# Lesson1_2.net
KiCad netlist of a schematic drawn in EasyEDA
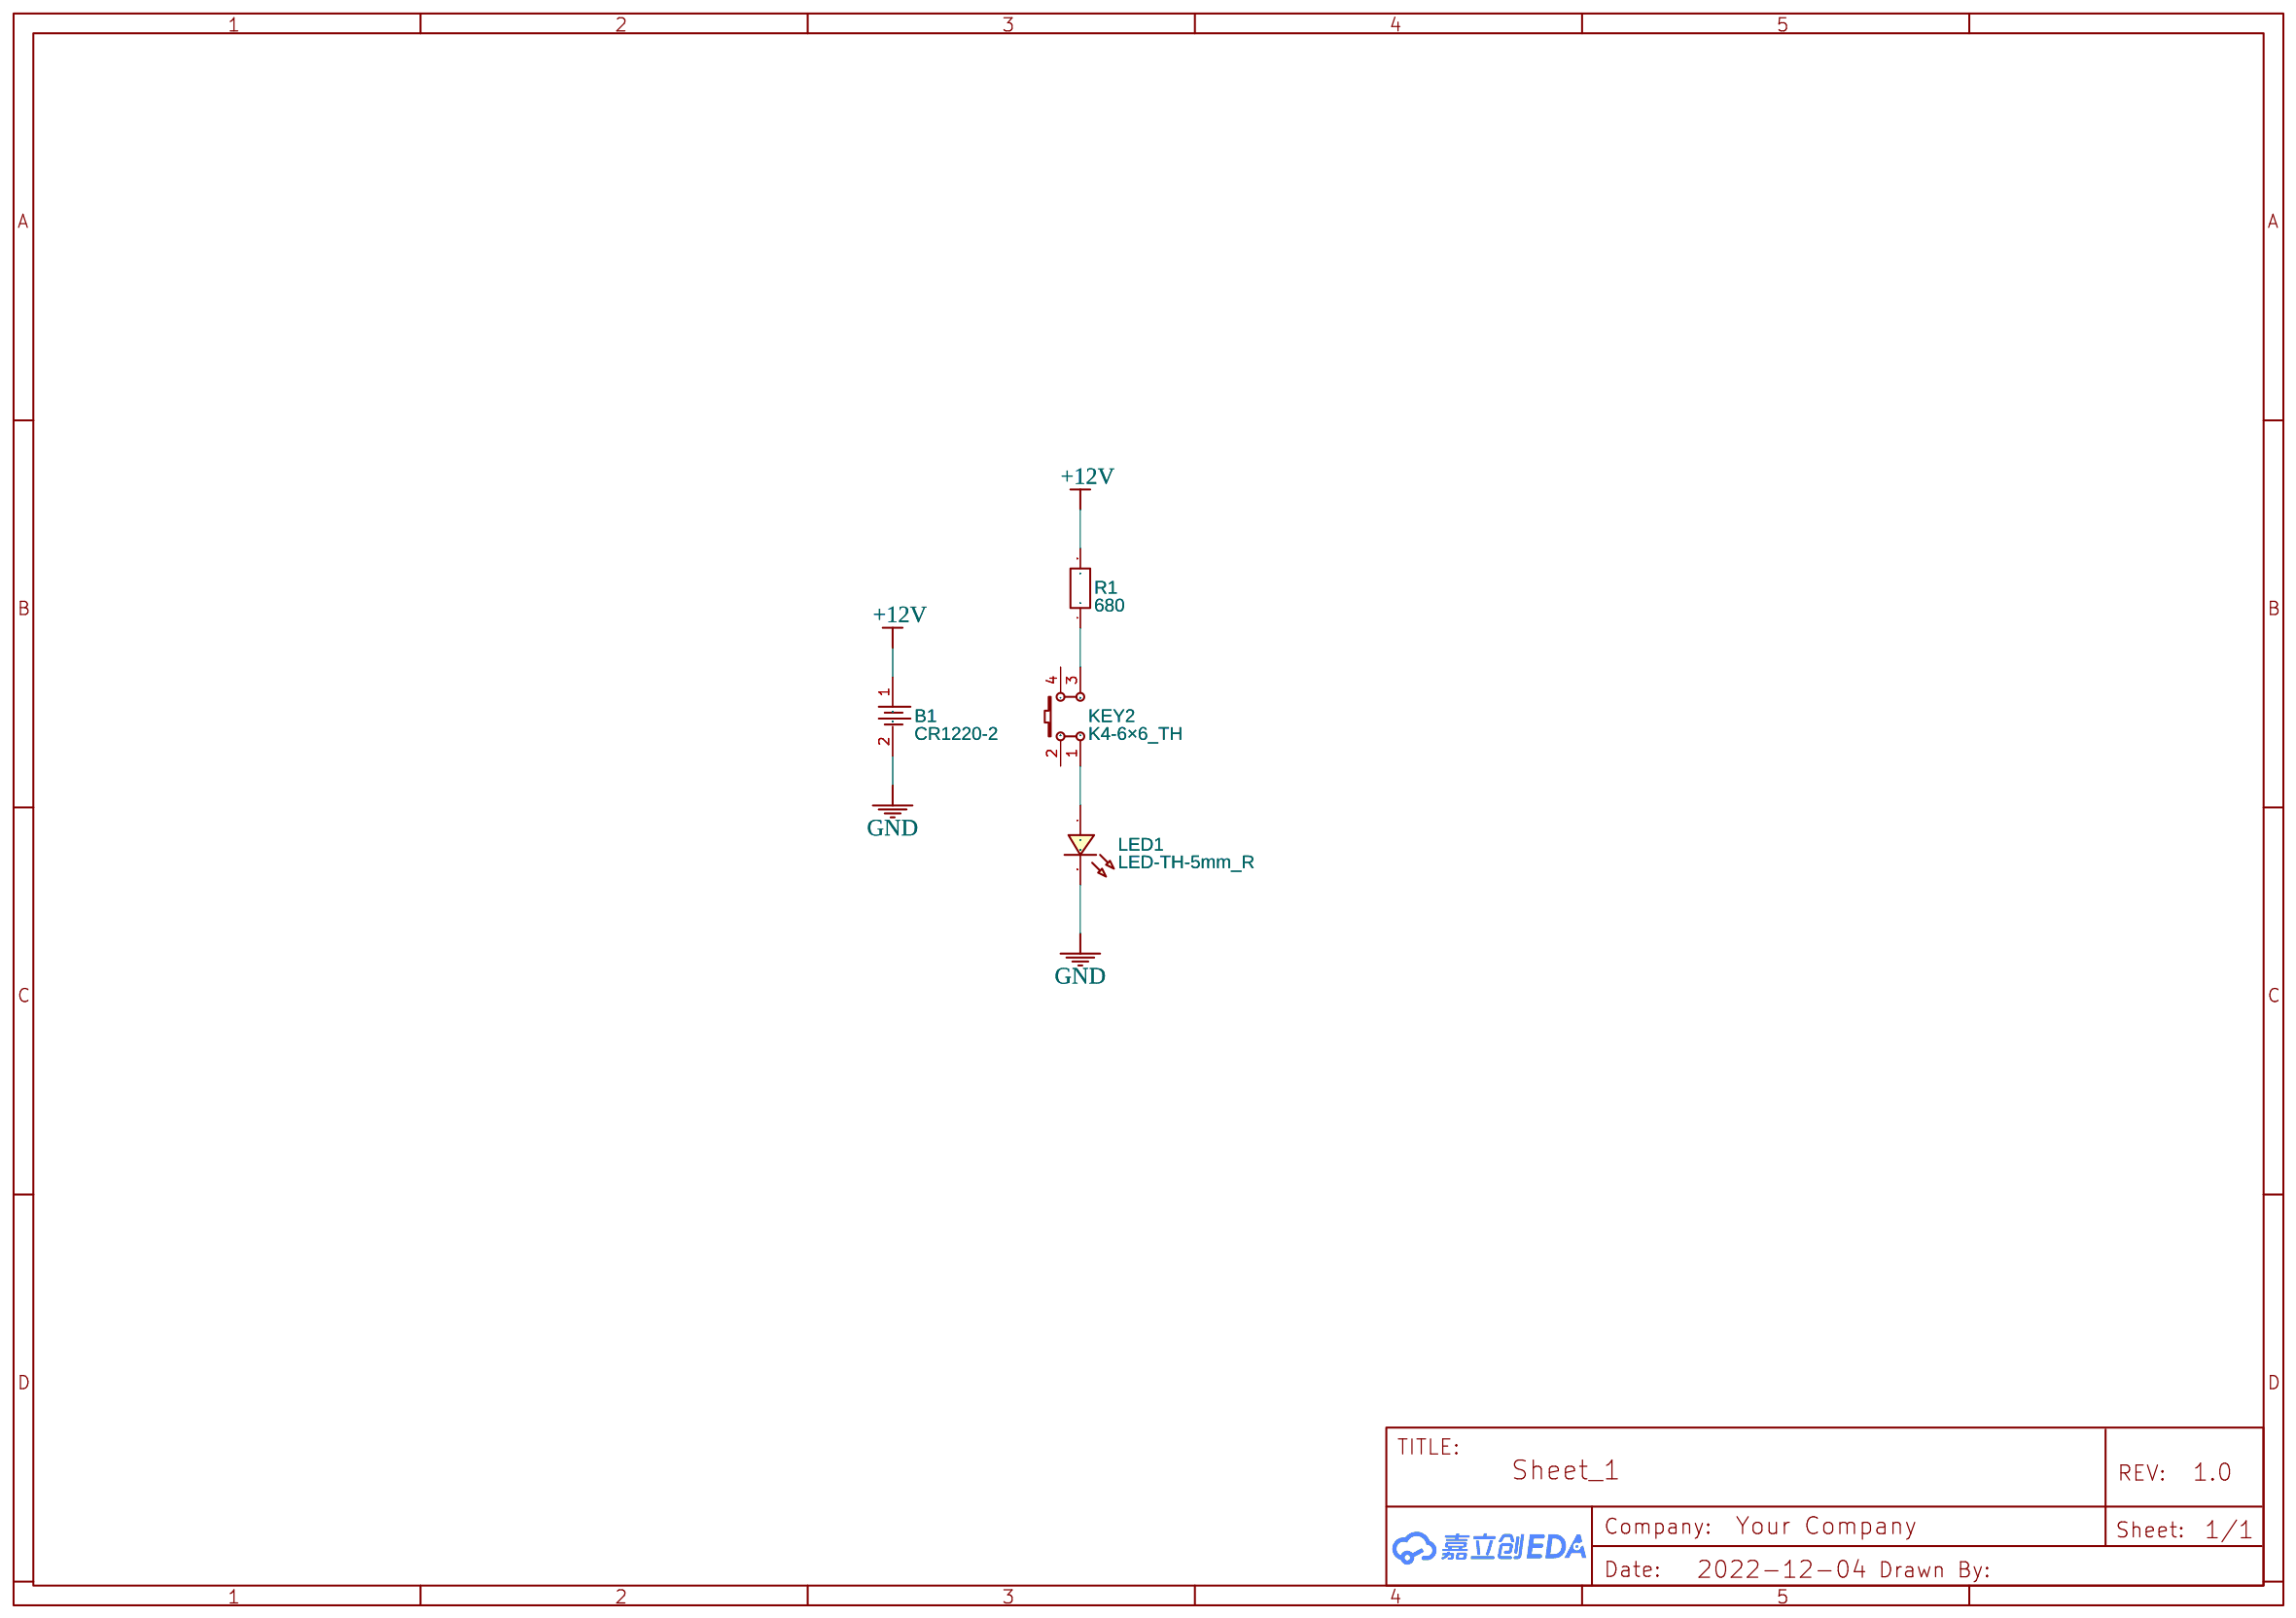
[diagram p0: schematic sheet]

(export (version "E")
  (design (tool "Eeschema 10.0.6"))
  (components
    (comp (ref "B1")
      (value "CR1220-2")
      (fields (field (name "BOM_Supplier Part") "C70381"))
      (libsource (lib "") (part "CR1220-2"))
    )
    (comp (ref "KEY2")
      (value "K4-6×6_TH")
      (fields
        (field (name "BOM_Manufacturer Part") "K2-1102DP-E4SW-04")
        (field (name "BOM_Supplier Part") "C136684")
      )
      (libsource (lib "") (part "K4-6×6_TH"))
    )
    (comp (ref "LED1")
      (value "LED-TH-5mm_R")
      (fields
        (field (name "BOM_Manufacturer Part") "333-2SURD/S530-A3")
        (field (name "BOM_Supplier Part") "C87271")
      )
      (libsource (lib "") (part "LED-TH-5mm_R"))
    )
    (comp (ref "R1") (value "680") (libsource (lib "") (part "R_AXIAL-1.0_EU")))
  )
  (nets
    (net (code "1") (name "+12V") (class "Default")
      (node (ref "B1") (pin "1") (pinfunction "1_1") (pintype "input"))
      (node (ref "R1") (pin "2") (pinfunction "2_2") (pintype "unspecified"))
    )
    (net (code "2") (name "GND") (class "Default")
      (node (ref "B1") (pin "2") (pinfunction "2_2") (pintype "input"))
      (node (ref "LED1") (pin "2") (pinfunction "2_2") (pintype "unspecified"))
    )
    (net (code "3") (name "Net-(KEY2-Pad1)") (class "Default")
      (node (ref "KEY2") (pin "1") (pinfunction "1_1") (pintype "unspecified"))
      (node (ref "LED1") (pin "1") (pinfunction "1_1") (pintype "unspecified"))
    )
    (net (code "4") (name "Net-(KEY2-Pad3)") (class "Default")
      (node (ref "KEY2") (pin "3") (pinfunction "3_3") (pintype "unspecified"))
      (node (ref "R1") (pin "1") (pinfunction "1_1") (pintype "unspecified"))
    )
    (net (code "5") (name "unconnected-(KEY2-Pad2)") (class "Default")
      (node (ref "KEY2") (pin "2") (pinfunction "2_2") (pintype "unspecified"))
    )
    (net (code "6") (name "unconnected-(KEY2-Pad4)") (class "Default")
      (node (ref "KEY2") (pin "4") (pinfunction "4_4") (pintype "unspecified"))
    )
  )
)
